# board_v1.net
KiCad netlist of a schematic drawn in EAGLE
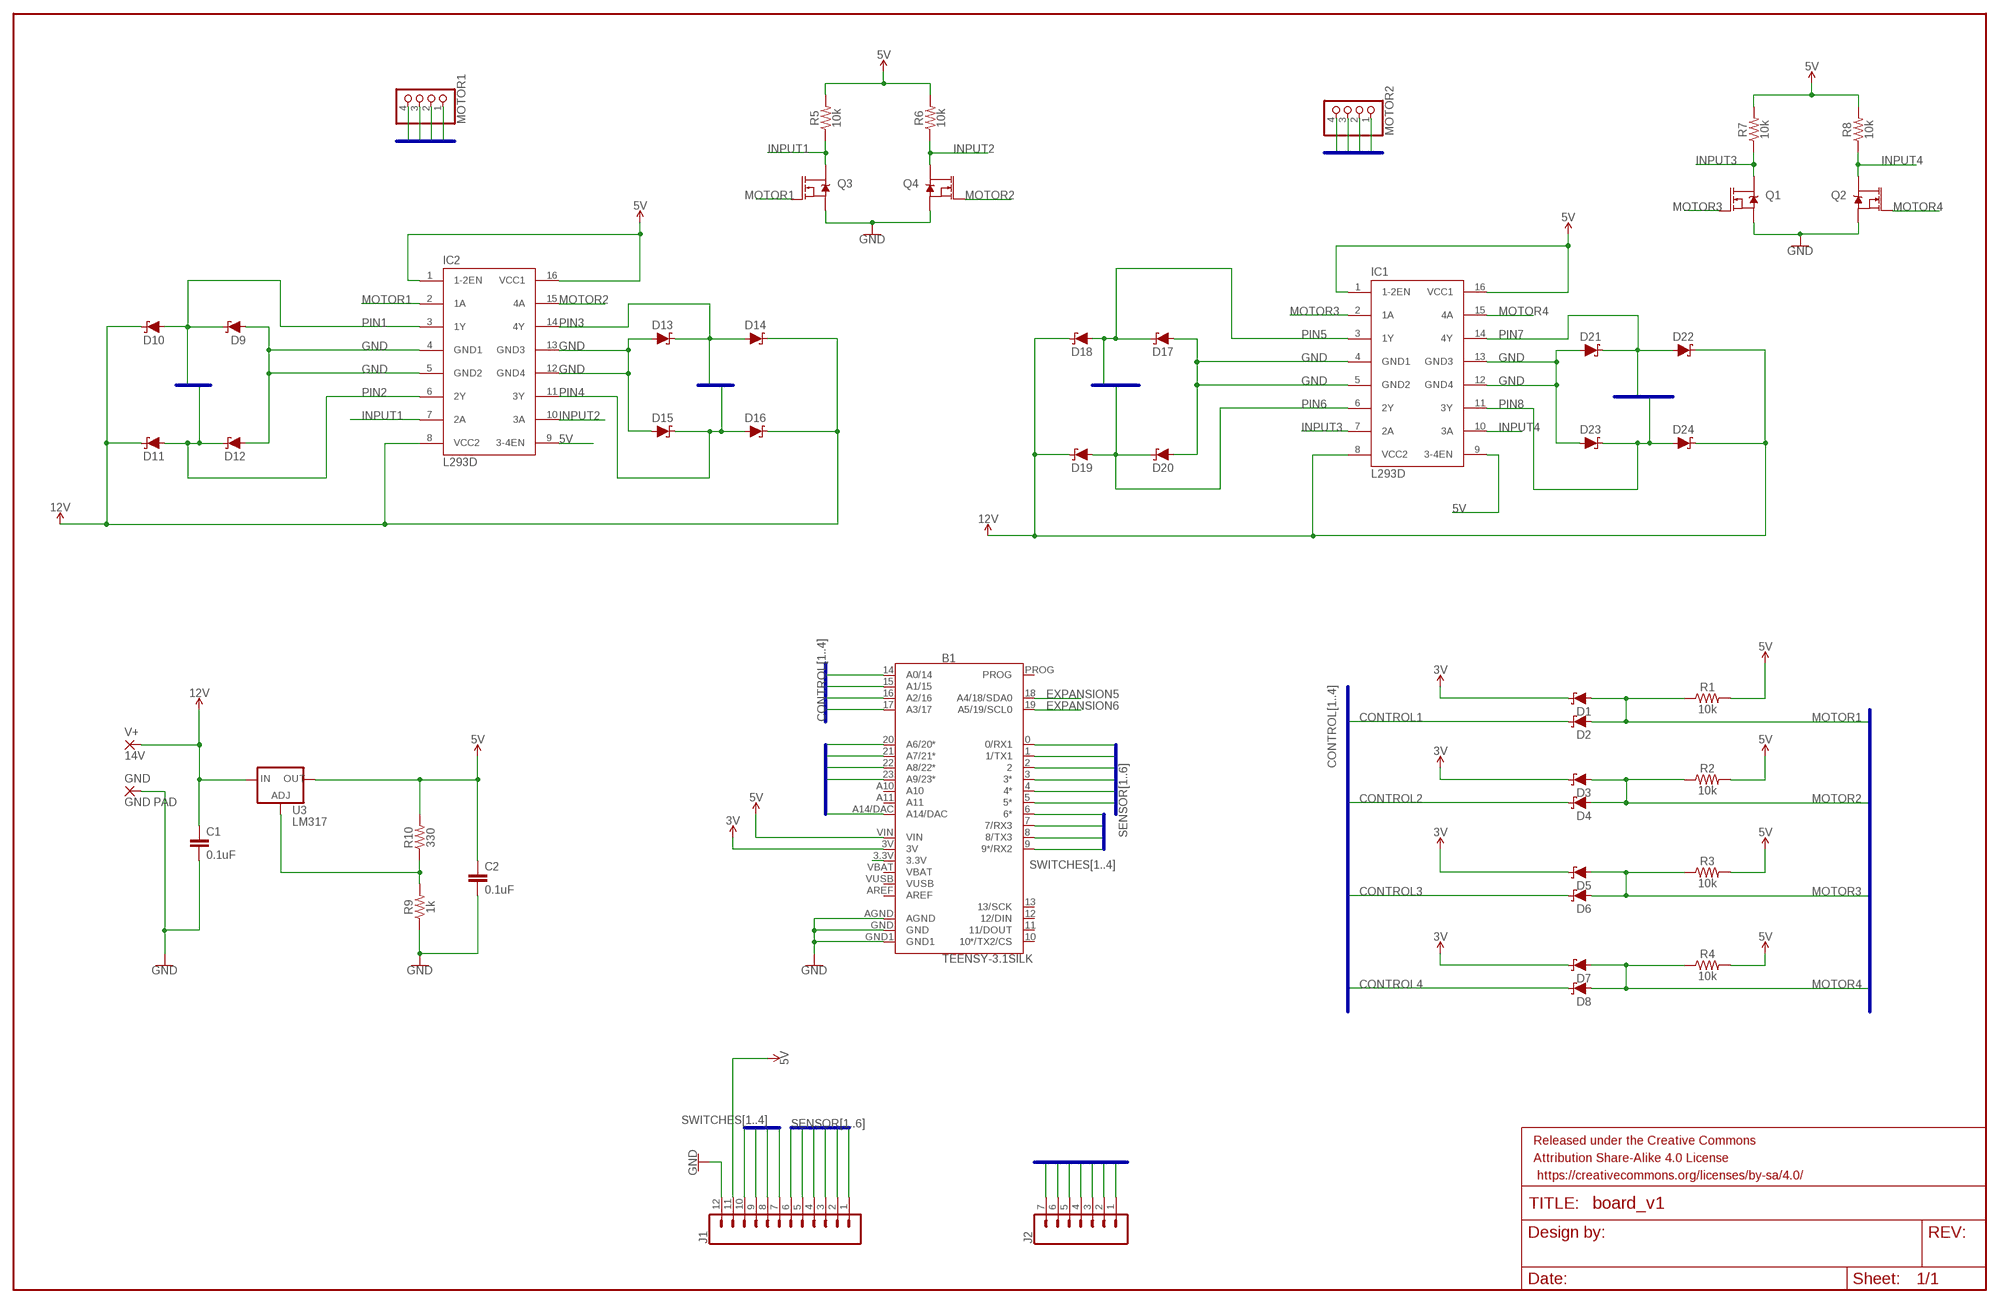
[diagram p0: schematic, sheet 1]

(export (version "E")
  (design (tool "Eeschema 10.0.6"))
  (components
    (comp (ref "B1")
      (value "TEENSY-3.1SILK")
      (footprint "eagle-import:TEENSY-3.1")
      (libsource (lib "eagle-import") (part "TEENSY-3.1SILK"))
    )
    (comp (ref "C1")
      (value "0.1uF")
      (footprint "eagle-import:0603")
      (libsource (lib "eagle-import") (part "0.1UF-0603-25V-5%"))
    )
    (comp (ref "C2")
      (value "0.1uF")
      (footprint "eagle-import:0603")
      (libsource (lib "eagle-import") (part "0.1UF-0603-25V-5%"))
    )
    (comp (ref "D1")
      (value "DIODE-SCHOTTKY-PMEG4005EJ")
      (footprint "eagle-import:SOD-323")
      (libsource (lib "eagle-import") (part "DIODE-SCHOTTKY-PMEG4005EJ"))
    )
    (comp (ref "D2")
      (value "DIODE-SCHOTTKY-PMEG4005EJ")
      (footprint "eagle-import:SOD-323")
      (libsource (lib "eagle-import") (part "DIODE-SCHOTTKY-PMEG4005EJ"))
    )
    (comp (ref "D3")
      (value "DIODE-SCHOTTKY-PMEG4005EJ")
      (footprint "eagle-import:SOD-323")
      (libsource (lib "eagle-import") (part "DIODE-SCHOTTKY-PMEG4005EJ"))
    )
    (comp (ref "D4")
      (value "DIODE-SCHOTTKY-PMEG4005EJ")
      (footprint "eagle-import:SOD-323")
      (libsource (lib "eagle-import") (part "DIODE-SCHOTTKY-PMEG4005EJ"))
    )
    (comp (ref "D5")
      (value "DIODE-SCHOTTKY-PMEG4005EJ")
      (footprint "eagle-import:SOD-323")
      (libsource (lib "eagle-import") (part "DIODE-SCHOTTKY-PMEG4005EJ"))
    )
    (comp (ref "D6")
      (value "DIODE-SCHOTTKY-PMEG4005EJ")
      (footprint "eagle-import:SOD-323")
      (libsource (lib "eagle-import") (part "DIODE-SCHOTTKY-PMEG4005EJ"))
    )
    (comp (ref "D7")
      (value "DIODE-SCHOTTKY-PMEG4005EJ")
      (footprint "eagle-import:SOD-323")
      (libsource (lib "eagle-import") (part "DIODE-SCHOTTKY-PMEG4005EJ"))
    )
    (comp (ref "D8")
      (value "DIODE-SCHOTTKY-PMEG4005EJ")
      (footprint "eagle-import:SOD-323")
      (libsource (lib "eagle-import") (part "DIODE-SCHOTTKY-PMEG4005EJ"))
    )
    (comp (ref "D9")
      (value "DIODE-SCHOTTKY-PMEG4005EJ")
      (footprint "eagle-import:SOD-323")
      (libsource (lib "eagle-import") (part "DIODE-SCHOTTKY-PMEG4005EJ"))
    )
    (comp (ref "D10")
      (value "DIODE-SCHOTTKY-PMEG4005EJ")
      (footprint "eagle-import:SOD-323")
      (libsource (lib "eagle-import") (part "DIODE-SCHOTTKY-PMEG4005EJ"))
    )
    (comp (ref "D11")
      (value "DIODE-SCHOTTKY-PMEG4005EJ")
      (footprint "eagle-import:SOD-323")
      (libsource (lib "eagle-import") (part "DIODE-SCHOTTKY-PMEG4005EJ"))
    )
    (comp (ref "D12")
      (value "DIODE-SCHOTTKY-PMEG4005EJ")
      (footprint "eagle-import:SOD-323")
      (libsource (lib "eagle-import") (part "DIODE-SCHOTTKY-PMEG4005EJ"))
    )
    (comp (ref "D13")
      (value "DIODE-SCHOTTKY-PMEG4005EJ")
      (footprint "eagle-import:SOD-323")
      (libsource (lib "eagle-import") (part "DIODE-SCHOTTKY-PMEG4005EJ"))
    )
    (comp (ref "D14")
      (value "DIODE-SCHOTTKY-PMEG4005EJ")
      (footprint "eagle-import:SOD-323")
      (libsource (lib "eagle-import") (part "DIODE-SCHOTTKY-PMEG4005EJ"))
    )
    (comp (ref "D15")
      (value "DIODE-SCHOTTKY-PMEG4005EJ")
      (footprint "eagle-import:SOD-323")
      (libsource (lib "eagle-import") (part "DIODE-SCHOTTKY-PMEG4005EJ"))
    )
    (comp (ref "D16")
      (value "DIODE-SCHOTTKY-PMEG4005EJ")
      (footprint "eagle-import:SOD-323")
      (libsource (lib "eagle-import") (part "DIODE-SCHOTTKY-PMEG4005EJ"))
    )
    (comp (ref "D17")
      (value "DIODE-SCHOTTKY-PMEG4005EJ")
      (footprint "eagle-import:SOD-323")
      (libsource (lib "eagle-import") (part "DIODE-SCHOTTKY-PMEG4005EJ"))
    )
    (comp (ref "D18")
      (value "DIODE-SCHOTTKY-PMEG4005EJ")
      (footprint "eagle-import:SOD-323")
      (libsource (lib "eagle-import") (part "DIODE-SCHOTTKY-PMEG4005EJ"))
    )
    (comp (ref "D19")
      (value "DIODE-SCHOTTKY-PMEG4005EJ")
      (footprint "eagle-import:SOD-323")
      (libsource (lib "eagle-import") (part "DIODE-SCHOTTKY-PMEG4005EJ"))
    )
    (comp (ref "D20")
      (value "DIODE-SCHOTTKY-PMEG4005EJ")
      (footprint "eagle-import:SOD-323")
      (libsource (lib "eagle-import") (part "DIODE-SCHOTTKY-PMEG4005EJ"))
    )
    (comp (ref "D21")
      (value "DIODE-SCHOTTKY-PMEG4005EJ")
      (footprint "eagle-import:SOD-323")
      (libsource (lib "eagle-import") (part "DIODE-SCHOTTKY-PMEG4005EJ"))
    )
    (comp (ref "D22")
      (value "DIODE-SCHOTTKY-PMEG4005EJ")
      (footprint "eagle-import:SOD-323")
      (libsource (lib "eagle-import") (part "DIODE-SCHOTTKY-PMEG4005EJ"))
    )
    (comp (ref "D23")
      (value "DIODE-SCHOTTKY-PMEG4005EJ")
      (footprint "eagle-import:SOD-323")
      (libsource (lib "eagle-import") (part "DIODE-SCHOTTKY-PMEG4005EJ"))
    )
    (comp (ref "D24")
      (value "DIODE-SCHOTTKY-PMEG4005EJ")
      (footprint "eagle-import:SOD-323")
      (libsource (lib "eagle-import") (part "DIODE-SCHOTTKY-PMEG4005EJ"))
    )
    (comp (ref "FRAME1")
      (value "FRAME-LEDGER")
      (footprint "eagle-import:CREATIVE_COMMONS")
      (libsource (lib "eagle-import") (part "FRAME-LEDGER"))
    )
    (comp (ref "GND")
      (value "GND PAD")
      (footprint "eagle-import:SMD2,54-5,08")
      (libsource (lib "eagle-import") (part "WIREPADSMD2,54-5,08"))
    )
    (comp (ref "IC1")
      (value "L293D")
      (footprint "eagle-import:DIL16")
      (libsource (lib "eagle-import") (part "L293D"))
    )
    (comp (ref "IC2")
      (value "L293D")
      (footprint "eagle-import:DIL16")
      (libsource (lib "eagle-import") (part "L293D"))
    )
    (comp (ref "J1")
      (value "CONN_12")
      (footprint "eagle-import:1X12")
      (libsource (lib "eagle-import") (part "CONN_12"))
    )
    (comp (ref "J2")
      (value "CONN_07LOCK")
      (footprint "eagle-import:1X07_LOCK")
      (libsource (lib "eagle-import") (part "CONN_07LOCK"))
    )
    (comp (ref "MOTOR1")
      (value "PINHD-1X4")
      (footprint "eagle-import:1X04")
      (libsource (lib "eagle-import") (part "PINHD-1X4"))
    )
    (comp (ref "MOTOR2")
      (value "PINHD-1X4")
      (footprint "eagle-import:1X04")
      (libsource (lib "eagle-import") (part "PINHD-1X4"))
    )
    (comp (ref "Q1")
      (value "MOSFET-NCH-2N7002PW")
      (footprint "eagle-import:SOT323")
      (libsource (lib "eagle-import") (part "MOSFET-NCH-2N7002PW"))
    )
    (comp (ref "Q2")
      (value "MOSFET-NCH-2N7002PW")
      (footprint "eagle-import:SOT323")
      (libsource (lib "eagle-import") (part "MOSFET-NCH-2N7002PW"))
    )
    (comp (ref "Q3")
      (value "MOSFET-NCH-2N7002PW")
      (footprint "eagle-import:SOT323")
      (libsource (lib "eagle-import") (part "MOSFET-NCH-2N7002PW"))
    )
    (comp (ref "Q4")
      (value "MOSFET-NCH-2N7002PW")
      (footprint "eagle-import:SOT323")
      (libsource (lib "eagle-import") (part "MOSFET-NCH-2N7002PW"))
    )
    (comp (ref "R1")
      (value "10k")
      (footprint "eagle-import:0603")
      (libsource (lib "eagle-import") (part "10KOHM-0603-1/10W-1%"))
    )
    (comp (ref "R2")
      (value "10k")
      (footprint "eagle-import:0603")
      (libsource (lib "eagle-import") (part "10KOHM-0603-1/10W-1%"))
    )
    (comp (ref "R3")
      (value "10k")
      (footprint "eagle-import:0603")
      (libsource (lib "eagle-import") (part "10KOHM-0603-1/10W-1%"))
    )
    (comp (ref "R4")
      (value "10k")
      (footprint "eagle-import:0603")
      (libsource (lib "eagle-import") (part "10KOHM-0603-1/10W-1%"))
    )
    (comp (ref "R5")
      (value "10k")
      (footprint "eagle-import:0603")
      (libsource (lib "eagle-import") (part "10KOHM-0603-1/10W-1%"))
    )
    (comp (ref "R6")
      (value "10k")
      (footprint "eagle-import:0603")
      (libsource (lib "eagle-import") (part "10KOHM-0603-1/10W-1%"))
    )
    (comp (ref "R7")
      (value "10k")
      (footprint "eagle-import:0603")
      (libsource (lib "eagle-import") (part "10KOHM-0603-1/10W-1%"))
    )
    (comp (ref "R8")
      (value "10k")
      (footprint "eagle-import:0603")
      (libsource (lib "eagle-import") (part "10KOHM-0603-1/10W-1%"))
    )
    (comp (ref "R9")
      (value "1k")
      (footprint "eagle-import:0603")
      (libsource (lib "eagle-import") (part "1KOHM-0603-1/10W-1%"))
    )
    (comp (ref "R10")
      (value "330")
      (footprint "eagle-import:0603")
      (libsource (lib "eagle-import") (part "3.3KOHM-0603-1/10W-1%"))
    )
    (comp (ref "U3")
      (value "LM317")
      (footprint "eagle-import:TO220-ADJ")
      (libsource (lib "eagle-import") (part "V_REG_317SINK"))
    )
    (comp (ref "V+")
      (value "14V")
      (footprint "eagle-import:SMD2,54-5,08")
      (libsource (lib "eagle-import") (part "WIREPADSMD2,54-5,08"))
    )
  )
  (nets
    (net (code "5") (name "3.3V") (class "Default")
      (node (ref "B1") (pin "3V") (pinfunction "3V_3V") (pintype "power_in"))
      (node (ref "D1") (pin "C") (pinfunction "C_C") (pintype "passive"))
      (node (ref "D3") (pin "C") (pinfunction "C_C") (pintype "passive"))
      (node (ref "D5") (pin "C") (pinfunction "C_C") (pintype "passive"))
      (node (ref "D7") (pin "C") (pinfunction "C_C") (pintype "passive"))
    )
    (net (code "6") (name "5V") (class "Default")
      (node (ref "B1") (pin "VIN") (pinfunction "VIN_VIN") (pintype "power_in"))
      (node (ref "C2") (pin "1") (pinfunction "1_1") (pintype "passive"))
      (node (ref "IC1") (pin "1") (pinfunction "1-2EN_1") (pintype "input"))
      (node (ref "IC1") (pin "16") (pinfunction "VCC1_16") (pintype "power_in"))
      (node (ref "IC1") (pin "9") (pinfunction "3-4EN_9") (pintype "input"))
      (node (ref "IC2") (pin "1") (pinfunction "1-2EN_1") (pintype "input"))
      (node (ref "IC2") (pin "16") (pinfunction "VCC1_16") (pintype "power_in"))
      (node (ref "IC2") (pin "9") (pinfunction "3-4EN_9") (pintype "input"))
      (node (ref "J1") (pin "11") (pinfunction "11_11") (pintype "passive"))
      (node (ref "R1") (pin "2") (pinfunction "2_2") (pintype "passive"))
      (node (ref "R10") (pin "2") (pinfunction "2_2") (pintype "passive"))
      (node (ref "R2") (pin "2") (pinfunction "2_2") (pintype "passive"))
      (node (ref "R3") (pin "2") (pinfunction "2_2") (pintype "passive"))
      (node (ref "R4") (pin "2") (pinfunction "2_2") (pintype "passive"))
      (node (ref "R5") (pin "2") (pinfunction "2_2") (pintype "passive"))
      (node (ref "R6") (pin "2") (pinfunction "2_2") (pintype "passive"))
      (node (ref "R7") (pin "2") (pinfunction "2_2") (pintype "passive"))
      (node (ref "R8") (pin "2") (pinfunction "2_2") (pintype "passive"))
      (node (ref "U3") (pin "OUT") (pinfunction "OUT_OUT") (pintype "output"))
    )
    (net (code "7") (name "12V") (class "Default")
      (node (ref "C1") (pin "1") (pinfunction "1_1") (pintype "passive"))
      (node (ref "D10") (pin "C") (pinfunction "C_C") (pintype "passive"))
      (node (ref "D11") (pin "C") (pinfunction "C_C") (pintype "passive"))
      (node (ref "D14") (pin "C") (pinfunction "C_C") (pintype "passive"))
      (node (ref "D16") (pin "C") (pinfunction "C_C") (pintype "passive"))
      (node (ref "D18") (pin "C") (pinfunction "C_C") (pintype "passive"))
      (node (ref "D19") (pin "C") (pinfunction "C_C") (pintype "passive"))
      (node (ref "D22") (pin "C") (pinfunction "C_C") (pintype "passive"))
      (node (ref "D24") (pin "C") (pinfunction "C_C") (pintype "passive"))
      (node (ref "IC1") (pin "8") (pinfunction "VCC2_8") (pintype "power_in"))
      (node (ref "IC2") (pin "8") (pinfunction "VCC2_8") (pintype "power_in"))
      (node (ref "U3") (pin "IN") (pinfunction "IN_IN") (pintype "input"))
      (node (ref "V+") (pin "1") (pinfunction "P_1") (pintype "passive"))
    )
    (net (code "8") (name "CONTROL1") (class "Default")
      (node (ref "B1") (pin "17") (pinfunction "A3/17_17") (pintype "bidirectional"))
      (node (ref "D2") (pin "C") (pinfunction "C_C") (pintype "passive"))
    )
    (net (code "9") (name "CONTROL2") (class "Default")
      (node (ref "B1") (pin "16") (pinfunction "A2/16_16") (pintype "bidirectional"))
      (node (ref "D4") (pin "C") (pinfunction "C_C") (pintype "passive"))
    )
    (net (code "10") (name "CONTROL3") (class "Default")
      (node (ref "B1") (pin "15") (pinfunction "A1/15_15") (pintype "bidirectional"))
      (node (ref "D6") (pin "C") (pinfunction "C_C") (pintype "passive"))
    )
    (net (code "11") (name "CONTROL4") (class "Default")
      (node (ref "B1") (pin "14") (pinfunction "A0/14_14") (pintype "bidirectional"))
      (node (ref "D8") (pin "C") (pinfunction "C_C") (pintype "passive"))
    )
    (net (code "12") (name "EXPANSION1") (class "Default")
      (node (ref "B1") (pin "20") (pinfunction "A6/20*_20") (pintype "bidirectional"))
      (node (ref "J2") (pin "1") (pinfunction "1_1") (pintype "passive"))
    )
    (net (code "13") (name "EXPANSION2") (class "Default")
      (node (ref "B1") (pin "21") (pinfunction "A7/21*_21") (pintype "bidirectional"))
      (node (ref "J2") (pin "2") (pinfunction "2_2") (pintype "passive"))
    )
    (net (code "14") (name "EXPANSION3") (class "Default")
      (node (ref "B1") (pin "22") (pinfunction "A8/22*_22") (pintype "bidirectional"))
      (node (ref "J2") (pin "3") (pinfunction "3_3") (pintype "passive"))
    )
    (net (code "15") (name "EXPANSION4") (class "Default")
      (node (ref "B1") (pin "23") (pinfunction "A9/23*_23") (pintype "bidirectional"))
      (node (ref "J2") (pin "4") (pinfunction "4_4") (pintype "passive"))
    )
    (net (code "16") (name "EXPANSION5") (class "Default")
      (node (ref "B1") (pin "18") (pinfunction "A4/18/SDA0_18") (pintype "bidirectional"))
      (node (ref "J2") (pin "5") (pinfunction "5_5") (pintype "passive"))
    )
    (net (code "17") (name "EXPANSION6") (class "Default")
      (node (ref "B1") (pin "19") (pinfunction "A5/19/SCL0_19") (pintype "bidirectional"))
      (node (ref "J2") (pin "6") (pinfunction "6_6") (pintype "passive"))
    )
    (net (code "18") (name "EXPANSION7") (class "Default")
      (node (ref "B1") (pin "A14/DAC") (pinfunction "A14/DAC_A14/DAC") (pintype "bidirectional"))
      (node (ref "J2") (pin "7") (pinfunction "7_7") (pintype "passive"))
    )
    (net (code "19") (name "GND") (class "Default")
      (node (ref "B1") (pin "AGND") (pinfunction "AGND_AGND") (pintype "power_in"))
      (node (ref "B1") (pin "GND") (pinfunction "GND_GND") (pintype "power_in"))
      (node (ref "B1") (pin "GND1") (pinfunction "GND1_GND1") (pintype "power_in"))
      (node (ref "C1") (pin "2") (pinfunction "2_2") (pintype "passive"))
      (node (ref "C2") (pin "2") (pinfunction "2_2") (pintype "passive"))
      (node (ref "D12") (pin "A") (pinfunction "A_A") (pintype "passive"))
      (node (ref "D13") (pin "A") (pinfunction "A_A") (pintype "passive"))
      (node (ref "D15") (pin "A") (pinfunction "A_A") (pintype "passive"))
      (node (ref "D17") (pin "A") (pinfunction "A_A") (pintype "passive"))
      (node (ref "D20") (pin "A") (pinfunction "A_A") (pintype "passive"))
      (node (ref "D21") (pin "A") (pinfunction "A_A") (pintype "passive"))
      (node (ref "D23") (pin "A") (pinfunction "A_A") (pintype "passive"))
      (node (ref "D9") (pin "A") (pinfunction "A_A") (pintype "passive"))
      (node (ref "GND") (pin "1") (pinfunction "P_1") (pintype "passive"))
      (node (ref "IC1") (pin "12") (pinfunction "GND4_12") (pintype "power_in"))
      (node (ref "IC1") (pin "13") (pinfunction "GND3_13") (pintype "power_in"))
      (node (ref "IC1") (pin "4") (pinfunction "GND1_4") (pintype "power_in"))
      (node (ref "IC1") (pin "5") (pinfunction "GND2_5") (pintype "power_in"))
      (node (ref "IC2") (pin "12") (pinfunction "GND4_12") (pintype "power_in"))
      (node (ref "IC2") (pin "13") (pinfunction "GND3_13") (pintype "power_in"))
      (node (ref "IC2") (pin "4") (pinfunction "GND1_4") (pintype "power_in"))
      (node (ref "IC2") (pin "5") (pinfunction "GND2_5") (pintype "power_in"))
      (node (ref "J1") (pin "12") (pinfunction "12_12") (pintype "passive"))
      (node (ref "Q1") (pin "2") (pinfunction "S_2") (pintype "bidirectional"))
      (node (ref "Q2") (pin "2") (pinfunction "S_2") (pintype "bidirectional"))
      (node (ref "Q3") (pin "2") (pinfunction "S_2") (pintype "bidirectional"))
      (node (ref "Q4") (pin "2") (pinfunction "S_2") (pintype "bidirectional"))
      (node (ref "R9") (pin "1") (pinfunction "1_1") (pintype "passive"))
    )
    (net (code "20") (name "INPUT1") (class "Default")
      (node (ref "IC2") (pin "7") (pinfunction "2A_7") (pintype "input"))
      (node (ref "Q3") (pin "3") (pinfunction "D_3") (pintype "bidirectional"))
      (node (ref "R5") (pin "1") (pinfunction "1_1") (pintype "passive"))
    )
    (net (code "21") (name "INPUT2") (class "Default")
      (node (ref "IC2") (pin "10") (pinfunction "3A_10") (pintype "input"))
      (node (ref "Q4") (pin "3") (pinfunction "D_3") (pintype "bidirectional"))
      (node (ref "R6") (pin "1") (pinfunction "1_1") (pintype "passive"))
    )
    (net (code "22") (name "INPUT3") (class "Default")
      (node (ref "IC1") (pin "7") (pinfunction "2A_7") (pintype "input"))
      (node (ref "Q1") (pin "3") (pinfunction "D_3") (pintype "bidirectional"))
      (node (ref "R7") (pin "1") (pinfunction "1_1") (pintype "passive"))
    )
    (net (code "23") (name "INPUT4") (class "Default")
      (node (ref "IC1") (pin "10") (pinfunction "3A_10") (pintype "input"))
      (node (ref "Q2") (pin "3") (pinfunction "D_3") (pintype "bidirectional"))
      (node (ref "R8") (pin "1") (pinfunction "1_1") (pintype "passive"))
    )
    (net (code "24") (name "MOTOR1") (class "Default")
      (node (ref "D1") (pin "A") (pinfunction "A_A") (pintype "passive"))
      (node (ref "D2") (pin "A") (pinfunction "A_A") (pintype "passive"))
      (node (ref "IC2") (pin "2") (pinfunction "1A_2") (pintype "input"))
      (node (ref "Q3") (pin "1") (pinfunction "G_1") (pintype "bidirectional"))
      (node (ref "R1") (pin "1") (pinfunction "1_1") (pintype "passive"))
    )
    (net (code "25") (name "MOTOR2") (class "Default")
      (node (ref "D3") (pin "A") (pinfunction "A_A") (pintype "passive"))
      (node (ref "D4") (pin "A") (pinfunction "A_A") (pintype "passive"))
      (node (ref "IC2") (pin "15") (pinfunction "4A_15") (pintype "input"))
      (node (ref "Q4") (pin "1") (pinfunction "G_1") (pintype "bidirectional"))
      (node (ref "R2") (pin "1") (pinfunction "1_1") (pintype "passive"))
    )
    (net (code "26") (name "MOTOR3") (class "Default")
      (node (ref "D5") (pin "A") (pinfunction "A_A") (pintype "passive"))
      (node (ref "D6") (pin "A") (pinfunction "A_A") (pintype "passive"))
      (node (ref "IC1") (pin "2") (pinfunction "1A_2") (pintype "input"))
      (node (ref "Q1") (pin "1") (pinfunction "G_1") (pintype "bidirectional"))
      (node (ref "R3") (pin "1") (pinfunction "1_1") (pintype "passive"))
    )
    (net (code "27") (name "MOTOR4") (class "Default")
      (node (ref "D7") (pin "A") (pinfunction "A_A") (pintype "passive"))
      (node (ref "D8") (pin "A") (pinfunction "A_A") (pintype "passive"))
      (node (ref "IC1") (pin "15") (pinfunction "4A_15") (pintype "input"))
      (node (ref "Q2") (pin "1") (pinfunction "G_1") (pintype "bidirectional"))
      (node (ref "R4") (pin "1") (pinfunction "1_1") (pintype "passive"))
    )
    (net (code "28") (name "Net-(R10-Pad1)") (class "Default")
      (node (ref "R10") (pin "1") (pinfunction "1_1") (pintype "passive"))
      (node (ref "R9") (pin "2") (pinfunction "2_2") (pintype "passive"))
      (node (ref "U3") (pin "ADJ") (pinfunction "ADJ_ADJ") (pintype "input"))
    )
    (net (code "29") (name "PIN1") (class "Default")
      (node (ref "D10") (pin "A") (pinfunction "A_A") (pintype "passive"))
      (node (ref "D9") (pin "C") (pinfunction "C_C") (pintype "passive"))
      (node (ref "IC2") (pin "3") (pinfunction "1Y_3") (pintype "output"))
      (node (ref "MOTOR1") (pin "4") (pinfunction "4_4") (pintype "passive"))
    )
    (net (code "30") (name "PIN2") (class "Default")
      (node (ref "D11") (pin "A") (pinfunction "A_A") (pintype "passive"))
      (node (ref "D12") (pin "C") (pinfunction "C_C") (pintype "passive"))
      (node (ref "IC2") (pin "6") (pinfunction "2Y_6") (pintype "output"))
      (node (ref "MOTOR1") (pin "3") (pinfunction "3_3") (pintype "passive"))
    )
    (net (code "31") (name "PIN3") (class "Default")
      (node (ref "D13") (pin "C") (pinfunction "C_C") (pintype "passive"))
      (node (ref "D14") (pin "A") (pinfunction "A_A") (pintype "passive"))
      (node (ref "IC2") (pin "14") (pinfunction "4Y_14") (pintype "output"))
      (node (ref "MOTOR1") (pin "2") (pinfunction "2_2") (pintype "passive"))
    )
    (net (code "32") (name "PIN4") (class "Default")
      (node (ref "D15") (pin "C") (pinfunction "C_C") (pintype "passive"))
      (node (ref "D16") (pin "A") (pinfunction "A_A") (pintype "passive"))
      (node (ref "IC2") (pin "11") (pinfunction "3Y_11") (pintype "output"))
      (node (ref "MOTOR1") (pin "1") (pinfunction "1_1") (pintype "passive"))
    )
    (net (code "33") (name "PIN5") (class "Default")
      (node (ref "D17") (pin "C") (pinfunction "C_C") (pintype "passive"))
      (node (ref "D18") (pin "A") (pinfunction "A_A") (pintype "passive"))
      (node (ref "IC1") (pin "3") (pinfunction "1Y_3") (pintype "output"))
      (node (ref "MOTOR2") (pin "4") (pinfunction "4_4") (pintype "passive"))
    )
    (net (code "34") (name "PIN6") (class "Default")
      (node (ref "D19") (pin "A") (pinfunction "A_A") (pintype "passive"))
      (node (ref "D20") (pin "C") (pinfunction "C_C") (pintype "passive"))
      (node (ref "IC1") (pin "6") (pinfunction "2Y_6") (pintype "output"))
      (node (ref "MOTOR2") (pin "3") (pinfunction "3_3") (pintype "passive"))
    )
    (net (code "35") (name "PIN7") (class "Default")
      (node (ref "D21") (pin "C") (pinfunction "C_C") (pintype "passive"))
      (node (ref "D22") (pin "A") (pinfunction "A_A") (pintype "passive"))
      (node (ref "IC1") (pin "14") (pinfunction "4Y_14") (pintype "output"))
      (node (ref "MOTOR2") (pin "2") (pinfunction "2_2") (pintype "passive"))
    )
    (net (code "36") (name "PIN8") (class "Default")
      (node (ref "D23") (pin "C") (pinfunction "C_C") (pintype "passive"))
      (node (ref "D24") (pin "A") (pinfunction "A_A") (pintype "passive"))
      (node (ref "IC1") (pin "11") (pinfunction "3Y_11") (pintype "output"))
      (node (ref "MOTOR2") (pin "1") (pinfunction "1_1") (pintype "passive"))
    )
    (net (code "37") (name "SENSOR1") (class "Default")
      (node (ref "B1") (pin "0") (pinfunction "0/RX1_0") (pintype "bidirectional"))
      (node (ref "J1") (pin "1") (pinfunction "1_1") (pintype "passive"))
    )
    (net (code "38") (name "SENSOR2") (class "Default")
      (node (ref "B1") (pin "1") (pinfunction "1/TX1_1") (pintype "bidirectional"))
      (node (ref "J1") (pin "2") (pinfunction "2_2") (pintype "passive"))
    )
    (net (code "39") (name "SENSOR3") (class "Default")
      (node (ref "B1") (pin "2") (pinfunction "2_2") (pintype "bidirectional"))
      (node (ref "J1") (pin "3") (pinfunction "3_3") (pintype "passive"))
    )
    (net (code "40") (name "SENSOR4") (class "Default")
      (node (ref "B1") (pin "3") (pinfunction "3*_3") (pintype "bidirectional"))
      (node (ref "J1") (pin "4") (pinfunction "4_4") (pintype "passive"))
    )
    (net (code "41") (name "SENSOR5") (class "Default")
      (node (ref "B1") (pin "4") (pinfunction "4*_4") (pintype "bidirectional"))
      (node (ref "J1") (pin "5") (pinfunction "5_5") (pintype "passive"))
    )
    (net (code "42") (name "SENSOR6") (class "Default")
      (node (ref "B1") (pin "5") (pinfunction "5*_5") (pintype "bidirectional"))
      (node (ref "J1") (pin "6") (pinfunction "6_6") (pintype "passive"))
    )
    (net (code "43") (name "SWITCHES1") (class "Default")
      (node (ref "B1") (pin "6") (pinfunction "6*_6") (pintype "bidirectional"))
      (node (ref "J1") (pin "7") (pinfunction "7_7") (pintype "passive"))
    )
    (net (code "44") (name "SWITCHES2") (class "Default")
      (node (ref "B1") (pin "7") (pinfunction "7/RX3_7") (pintype "bidirectional"))
      (node (ref "J1") (pin "8") (pinfunction "8_8") (pintype "passive"))
    )
    (net (code "45") (name "SWITCHES3") (class "Default")
      (node (ref "B1") (pin "8") (pinfunction "8/TX3_8") (pintype "bidirectional"))
      (node (ref "J1") (pin "9") (pinfunction "9_9") (pintype "passive"))
    )
    (net (code "46") (name "SWITCHES4") (class "Default")
      (node (ref "B1") (pin "9") (pinfunction "9*/RX2_9") (pintype "bidirectional"))
      (node (ref "J1") (pin "10") (pinfunction "10_10") (pintype "passive"))
    )
    (net (code "47") (name "VBAT") (class "Default")
      (node (ref "B1") (pin "VBAT") (pinfunction "VBAT_VBAT") (pintype "power_in"))
    )
    (net (code "48") (name "VUSB") (class "Default")
      (node (ref "B1") (pin "VUSB") (pinfunction "VUSB_VUSB") (pintype "power_in"))
    )
    (net (code "49") (name "unconnected-(B1-10*{slash}TX2{slash}CS-Pad10)") (class "Default")
      (node (ref "B1") (pin "10") (pinfunction "10*/TX2/CS_10") (pintype "bidirectional"))
    )
    (net (code "50") (name "unconnected-(B1-11{slash}DOUT-Pad11)") (class "Default")
      (node (ref "B1") (pin "11") (pinfunction "11/DOUT_11") (pintype "bidirectional"))
    )
    (net (code "51") (name "unconnected-(B1-12{slash}DIN-Pad12)") (class "Default")
      (node (ref "B1") (pin "12") (pinfunction "12/DIN_12") (pintype "bidirectional"))
    )
    (net (code "52") (name "unconnected-(B1-13{slash}SCK-Pad13)") (class "Default")
      (node (ref "B1") (pin "13") (pinfunction "13/SCK_13") (pintype "bidirectional"))
    )
    (net (code "53") (name "unconnected-(B1-Pad3.3V)") (class "Default")
      (node (ref "B1") (pin "3.3V") (pinfunction "3.3V_3.3V") (pintype "power_in"))
    )
    (net (code "54") (name "unconnected-(B1-PadA10)") (class "Default")
      (node (ref "B1") (pin "A10") (pinfunction "A10_A10") (pintype "bidirectional"))
    )
    (net (code "55") (name "unconnected-(B1-PadA11)") (class "Default")
      (node (ref "B1") (pin "A11") (pinfunction "A11_A11") (pintype "bidirectional"))
    )
    (net (code "56") (name "unconnected-(B1-PadAREF)") (class "Default")
      (node (ref "B1") (pin "AREF") (pinfunction "AREF_AREF") (pintype "bidirectional"))
    )
    (net (code "57") (name "unconnected-(B1-PadPROG)") (class "Default")
      (node (ref "B1") (pin "PROG") (pinfunction "PROG_PROG") (pintype "bidirectional"))
    )
  )
)
